# Lab_Controller_Board_v03.net
KiCad netlist of a schematic drawn in EAGLE
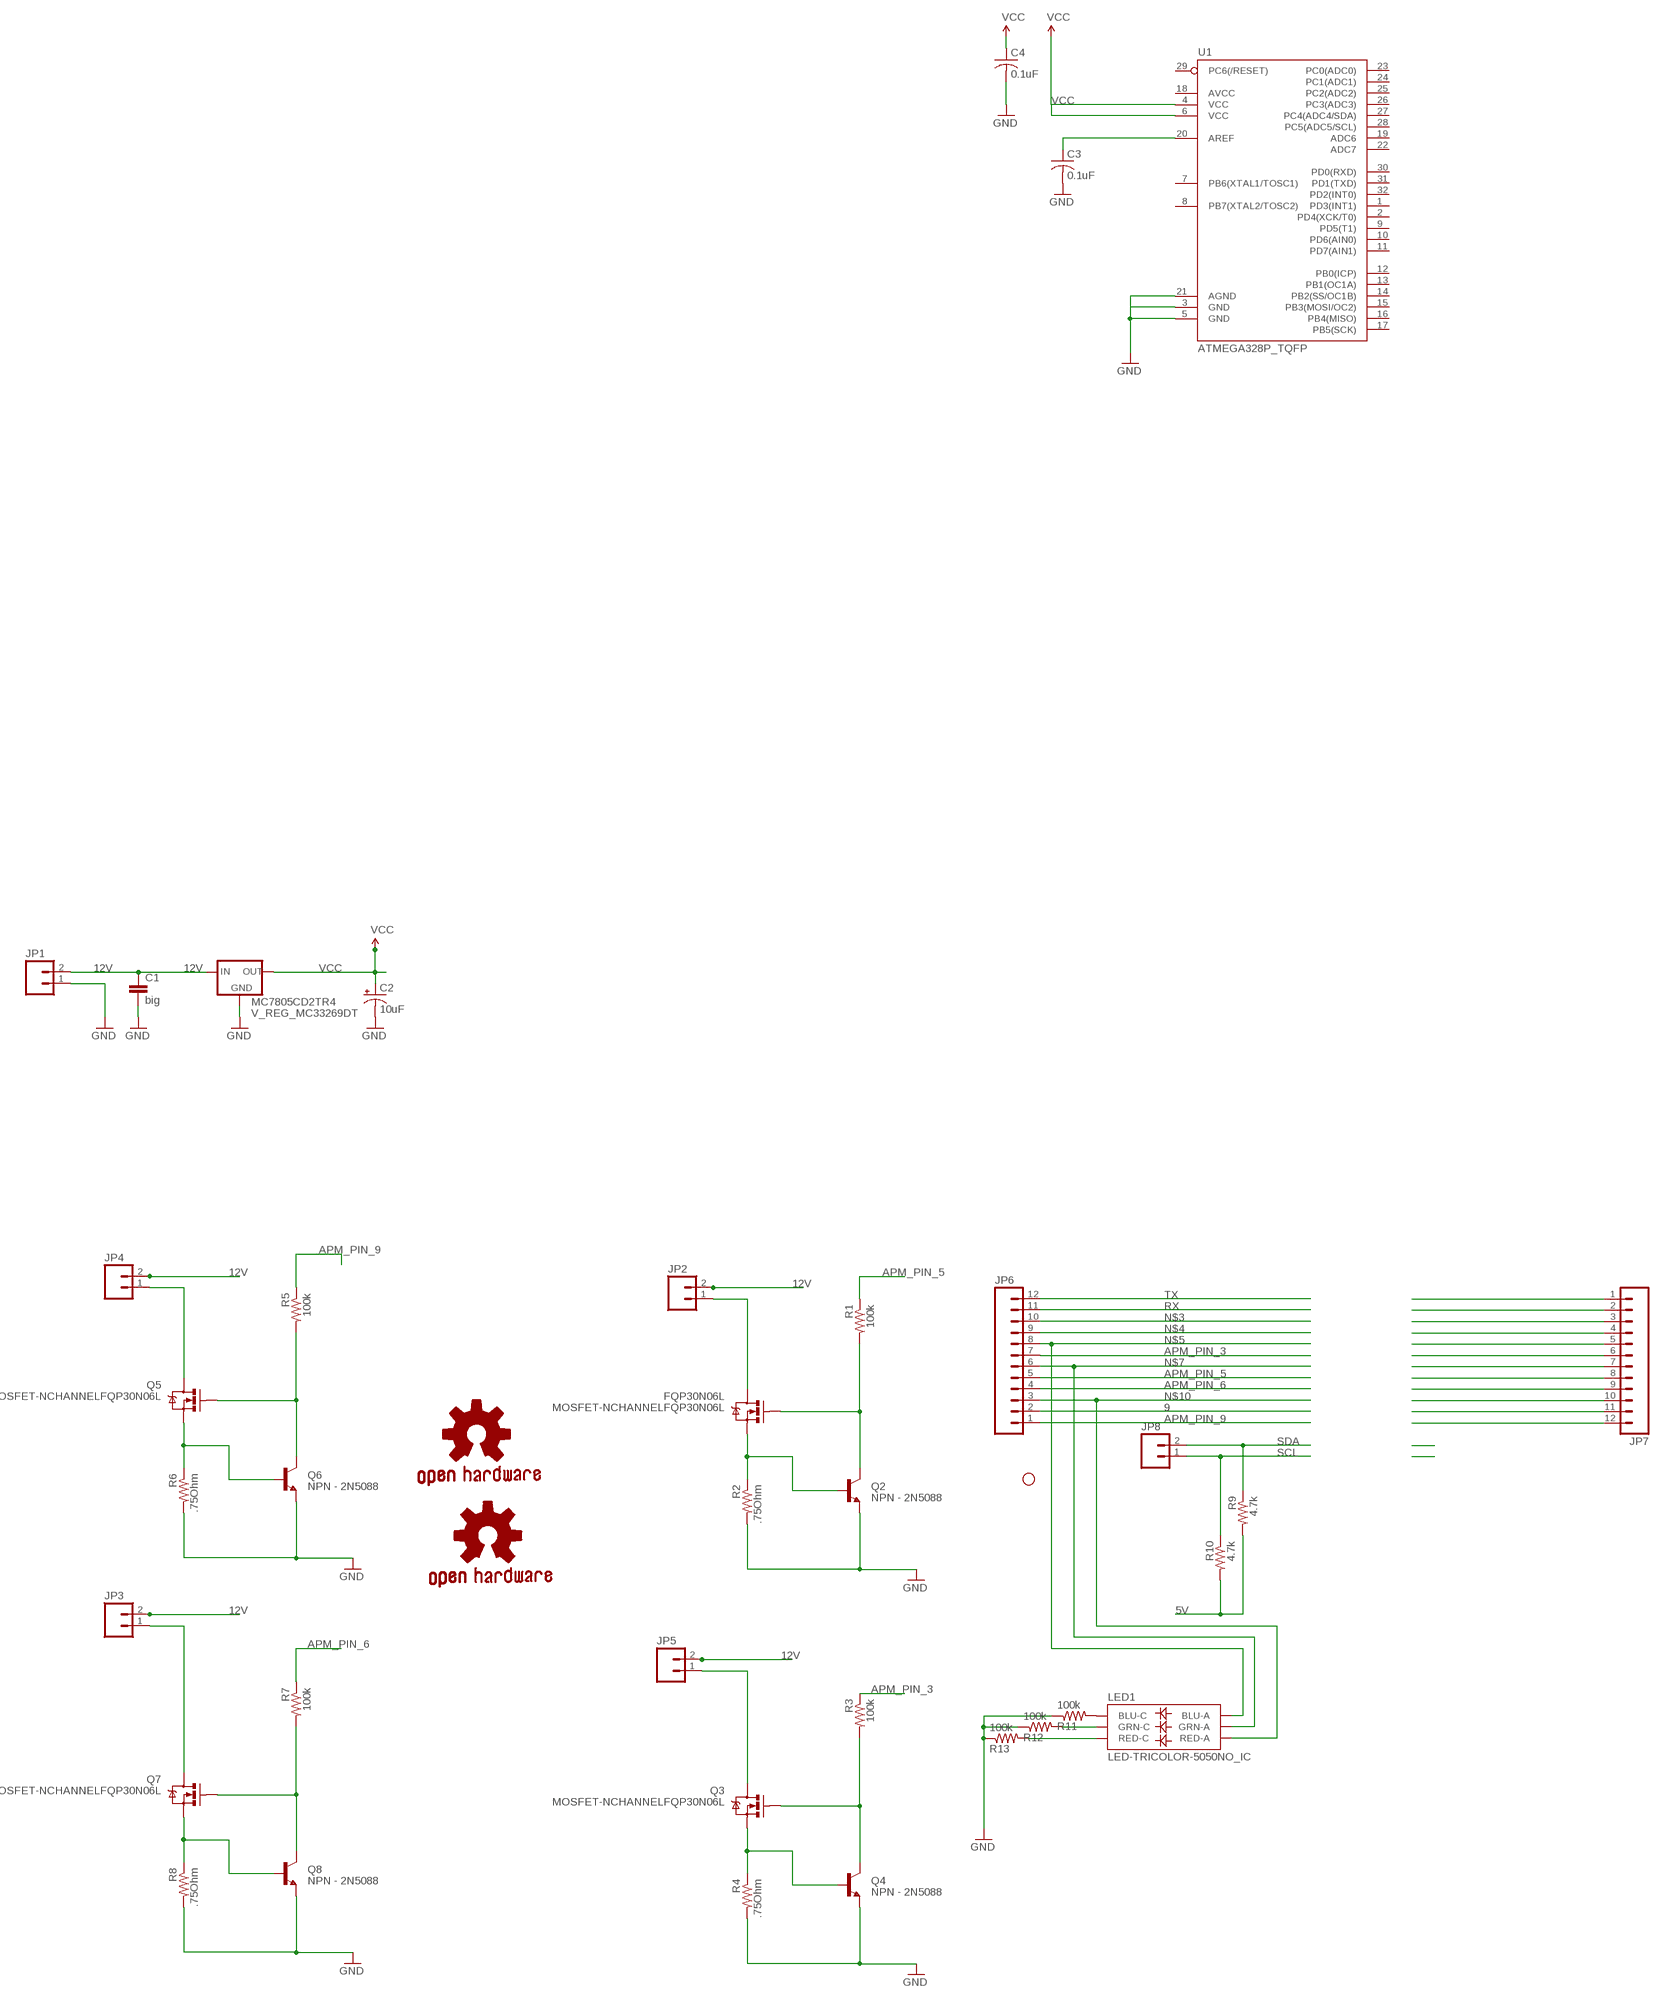
[diagram p0: schematic, sheet 1]

(export (version "E")
  (design (tool "Eeschema 10.0.6"))
  (components
    (comp (ref "C1")
      (value "big")
      (footprint "eagle-import:CAP-PTH-5MM")
      (libsource (lib "eagle-import") (part "CAPPTH1"))
    )
    (comp (ref "C2")
      (value "10uF")
      (footprint "eagle-import:EIA3528")
      (libsource (lib "eagle-import") (part "CAP_POL3528"))
    )
    (comp (ref "C3")
      (value "0.1uF")
      (footprint "eagle-import:C0402")
      (libsource (lib "eagle-import") (part "C-USC0402"))
    )
    (comp (ref "C4")
      (value "0.1uF")
      (footprint "eagle-import:C0402")
      (libsource (lib "eagle-import") (part "C-USC0402"))
    )
    (comp (ref "FQP30N06L")
      (value "MOSFET-NCHANNELFQP30N06L")
      (footprint "eagle-import:TO220V")
      (libsource (lib "eagle-import") (part "MOSFET-NCHANNELFQP30N06L"))
    )
    (comp (ref "GOLD_ORB_SM1")
      (value "OSHWLOGO_GOLD_ORB_MED")
      (footprint "eagle-import:OSHW1")
      (libsource (lib "eagle-import") (part "OSHWLOGO_GOLD_ORB_MED"))
    )
    (comp (ref "GOLD_ORB_SM2")
      (value "OSHWLOGO_GOLD_ORB_SM")
      (footprint "eagle-import:OSHW2")
      (libsource (lib "eagle-import") (part "OSHWLOGO_GOLD_ORB_SM"))
    )
    (comp (ref "JP1")
      (value "M025MM")
      (footprint "eagle-import:SCREWTERMINAL-5MM-2")
      (libsource (lib "eagle-import") (part "M025MM"))
    )
    (comp (ref "JP2")
      (value "M025MM")
      (footprint "eagle-import:SCREWTERMINAL-5MM-2")
      (libsource (lib "eagle-import") (part "M025MM"))
    )
    (comp (ref "JP3")
      (value "M025MM")
      (footprint "eagle-import:SCREWTERMINAL-5MM-2")
      (libsource (lib "eagle-import") (part "M025MM"))
    )
    (comp (ref "JP4")
      (value "M025MM")
      (footprint "eagle-import:SCREWTERMINAL-5MM-2")
      (libsource (lib "eagle-import") (part "M025MM"))
    )
    (comp (ref "JP5")
      (value "M025MM")
      (footprint "eagle-import:SCREWTERMINAL-5MM-2")
      (libsource (lib "eagle-import") (part "M025MM"))
    )
    (comp (ref "JP6")
      (value "M12PTH")
      (footprint "eagle-import:1X12")
      (libsource (lib "eagle-import") (part "M12PTH"))
    )
    (comp (ref "JP7")
      (value "M12PTH")
      (footprint "eagle-import:1X12")
      (libsource (lib "eagle-import") (part "M12PTH"))
    )
    (comp (ref "JP8")
      (value "M02LOCK")
      (footprint "eagle-import:1X02_LOCK")
      (libsource (lib "eagle-import") (part "M02LOCK"))
    )
    (comp (ref "LED1")
      (value "LED-TRICOLOR-5050NO_IC")
      (footprint "eagle-import:LED-TRICOLOR-5050")
      (libsource (lib "eagle-import") (part "LED-TRICOLOR-5050NO_IC"))
    )
    (comp (ref "MC7805CD2TR4")
      (value "V_REG_MC33269DT")
      (footprint "eagle-import:DPAK")
      (libsource (lib "eagle-import") (part "V_REG_MC33269DT"))
    )
    (comp (ref "Q2")
      (value "NPN - 2N5088")
      (footprint "eagle-import:TO-92")
      (libsource (lib "eagle-import") (part "TRANSISTOR_NPNTO92"))
    )
    (comp (ref "Q3")
      (value "MOSFET-NCHANNELFQP30N06L")
      (footprint "eagle-import:TO220V")
      (libsource (lib "eagle-import") (part "MOSFET-NCHANNELFQP30N06L"))
    )
    (comp (ref "Q4")
      (value "NPN - 2N5088")
      (footprint "eagle-import:TO-92")
      (libsource (lib "eagle-import") (part "TRANSISTOR_NPNTO92"))
    )
    (comp (ref "Q5")
      (value "MOSFET-NCHANNELFQP30N06L")
      (footprint "eagle-import:TO220V")
      (libsource (lib "eagle-import") (part "MOSFET-NCHANNELFQP30N06L"))
    )
    (comp (ref "Q6")
      (value "NPN - 2N5088")
      (footprint "eagle-import:TO-92")
      (libsource (lib "eagle-import") (part "TRANSISTOR_NPNTO92"))
    )
    (comp (ref "Q7")
      (value "MOSFET-NCHANNELFQP30N06L")
      (footprint "eagle-import:TO220V")
      (libsource (lib "eagle-import") (part "MOSFET-NCHANNELFQP30N06L"))
    )
    (comp (ref "Q8")
      (value "NPN - 2N5088")
      (footprint "eagle-import:TO-92")
      (libsource (lib "eagle-import") (part "TRANSISTOR_NPNTO92"))
    )
    (comp (ref "R1")
      (value "100k")
      (footprint "eagle-import:R0805W")
      (libsource (lib "eagle-import") (part "R-US_R0805W"))
    )
    (comp (ref "R2")
      (value ".75Ohm")
      (footprint "eagle-import:0411V")
      (libsource (lib "eagle-import") (part "R-US_0411/3V"))
    )
    (comp (ref "R3")
      (value "100k")
      (footprint "eagle-import:R0805W")
      (libsource (lib "eagle-import") (part "R-US_R0805W"))
    )
    (comp (ref "R4")
      (value ".75Ohm")
      (footprint "eagle-import:0411V")
      (libsource (lib "eagle-import") (part "R-US_0411/3V"))
    )
    (comp (ref "R5")
      (value "100k")
      (footprint "eagle-import:R0805W")
      (libsource (lib "eagle-import") (part "R-US_R0805W"))
    )
    (comp (ref "R6")
      (value ".75Ohm")
      (footprint "eagle-import:0411V")
      (libsource (lib "eagle-import") (part "R-US_0411/3V"))
    )
    (comp (ref "R7")
      (value "100k")
      (footprint "eagle-import:R0805W")
      (libsource (lib "eagle-import") (part "R-US_R0805W"))
    )
    (comp (ref "R8")
      (value ".75Ohm")
      (footprint "eagle-import:0411V")
      (libsource (lib "eagle-import") (part "R-US_0411/3V"))
    )
    (comp (ref "R9")
      (value "4.7k")
      (footprint "eagle-import:M0805")
      (libsource (lib "eagle-import") (part "R-US_M0805"))
    )
    (comp (ref "R10")
      (value "4.7k")
      (footprint "eagle-import:M0805")
      (libsource (lib "eagle-import") (part "R-US_M0805"))
    )
    (comp (ref "R11")
      (value "100k")
      (footprint "eagle-import:R0805W")
      (libsource (lib "eagle-import") (part "R-US_R0805W"))
    )
    (comp (ref "R12")
      (value "100k")
      (footprint "eagle-import:R0805W")
      (libsource (lib "eagle-import") (part "R-US_R0805W"))
    )
    (comp (ref "R13")
      (value "100k")
      (footprint "eagle-import:R0805W")
      (libsource (lib "eagle-import") (part "R-US_R0805W"))
    )
    (comp (ref "STANDOFF1")
      (value "STAND-OFF")
      (footprint "eagle-import:STAND-OFF")
      (libsource (lib "eagle-import") (part "STAND-OFF"))
    )
    (comp (ref "U1")
      (value "ATMEGA328P_TQFP")
      (footprint "eagle-import:TQFP32-08")
      (libsource (lib "eagle-import") (part "ATMEGA328P_TQFP"))
    )
  )
  (nets
    (net (code "1") (name "/5V") (class "Default")
      (node (ref "R10") (pin "2") (pinfunction "2_2") (pintype "passive"))
      (node (ref "R9") (pin "2") (pinfunction "2_2") (pintype "passive"))
    )
    (net (code "2") (name "/9") (class "Default")
      (node (ref "JP6") (pin "2") (pinfunction "2_2") (pintype "passive"))
    )
    (net (code "3") (name "/12V") (class "Default")
      (node (ref "C1") (pin "1") (pinfunction "1_1") (pintype "passive"))
      (node (ref "JP1") (pin "2") (pinfunction "2_2") (pintype "passive"))
      (node (ref "JP2") (pin "2") (pinfunction "2_2") (pintype "passive"))
      (node (ref "JP3") (pin "2") (pinfunction "2_2") (pintype "passive"))
      (node (ref "JP4") (pin "2") (pinfunction "2_2") (pintype "passive"))
      (node (ref "JP5") (pin "2") (pinfunction "2_2") (pintype "passive"))
      (node (ref "MC7805CD2TR4") (pin "3") (pinfunction "IN_3") (pintype "input"))
    )
    (net (code "4") (name "/APM_PIN_3") (class "Default")
      (node (ref "JP6") (pin "7") (pinfunction "7_7") (pintype "passive"))
      (node (ref "R3") (pin "1") (pinfunction "1_1") (pintype "passive"))
    )
    (net (code "5") (name "/APM_PIN_5") (class "Default")
      (node (ref "JP6") (pin "5") (pinfunction "5_5") (pintype "passive"))
      (node (ref "R1") (pin "1") (pinfunction "1_1") (pintype "passive"))
    )
    (net (code "6") (name "/APM_PIN_6") (class "Default")
      (node (ref "JP6") (pin "4") (pinfunction "4_4") (pintype "passive"))
      (node (ref "R7") (pin "1") (pinfunction "1_1") (pintype "passive"))
    )
    (net (code "7") (name "/APM_PIN_9") (class "Default")
      (node (ref "JP6") (pin "1") (pinfunction "1_1") (pintype "passive"))
      (node (ref "R5") (pin "1") (pinfunction "1_1") (pintype "passive"))
    )
    (net (code "8") (name "/N$3") (class "Default")
      (node (ref "JP6") (pin "10") (pinfunction "10_10") (pintype "passive"))
    )
    (net (code "9") (name "/N$4") (class "Default")
      (node (ref "JP6") (pin "9") (pinfunction "9_9") (pintype "passive"))
    )
    (net (code "10") (name "/N$5") (class "Default")
      (node (ref "JP6") (pin "8") (pinfunction "8_8") (pintype "passive"))
      (node (ref "LED1") (pin "3") (pinfunction "BLU-A_3") (pintype "bidirectional"))
    )
    (net (code "11") (name "/N$7") (class "Default")
      (node (ref "JP6") (pin "6") (pinfunction "6_6") (pintype "passive"))
      (node (ref "LED1") (pin "1") (pinfunction "GRN-A_1") (pintype "bidirectional"))
    )
    (net (code "12") (name "/N$10") (class "Default")
      (node (ref "JP6") (pin "3") (pinfunction "3_3") (pintype "passive"))
      (node (ref "LED1") (pin "2") (pinfunction "RED-A_2") (pintype "bidirectional"))
    )
    (net (code "13") (name "/RX") (class "Default")
      (node (ref "JP6") (pin "11") (pinfunction "11_11") (pintype "passive"))
    )
    (net (code "14") (name "/SCL") (class "Default")
      (node (ref "JP8") (pin "1") (pinfunction "1_1") (pintype "passive"))
      (node (ref "R10") (pin "1") (pinfunction "1_1") (pintype "passive"))
    )
    (net (code "15") (name "/SDA") (class "Default")
      (node (ref "JP8") (pin "2") (pinfunction "2_2") (pintype "passive"))
      (node (ref "R9") (pin "1") (pinfunction "1_1") (pintype "passive"))
    )
    (net (code "16") (name "/TX") (class "Default")
      (node (ref "JP6") (pin "12") (pinfunction "12_12") (pintype "passive"))
    )
    (net (code "17") (name "GND") (class "Default")
      (node (ref "C1") (pin "2") (pinfunction "2_2") (pintype "passive"))
      (node (ref "C2") (pin "C") (pinfunction "-_C") (pintype "passive"))
      (node (ref "C3") (pin "2") (pinfunction "2_2") (pintype "passive"))
      (node (ref "C4") (pin "2") (pinfunction "2_2") (pintype "passive"))
      (node (ref "JP1") (pin "1") (pinfunction "1_1") (pintype "passive"))
      (node (ref "MC7805CD2TR4") (pin "1") (pinfunction "GND_1") (pintype "input"))
      (node (ref "Q2") (pin "1") (pinfunction "E_1") (pintype "passive"))
      (node (ref "Q4") (pin "1") (pinfunction "E_1") (pintype "passive"))
      (node (ref "Q6") (pin "1") (pinfunction "E_1") (pintype "passive"))
      (node (ref "Q8") (pin "1") (pinfunction "E_1") (pintype "passive"))
      (node (ref "R11") (pin "1") (pinfunction "1_1") (pintype "passive"))
      (node (ref "R12") (pin "1") (pinfunction "1_1") (pintype "passive"))
      (node (ref "R13") (pin "1") (pinfunction "1_1") (pintype "passive"))
      (node (ref "R2") (pin "2") (pinfunction "2_2") (pintype "passive"))
      (node (ref "R4") (pin "2") (pinfunction "2_2") (pintype "passive"))
      (node (ref "R6") (pin "2") (pinfunction "2_2") (pintype "passive"))
      (node (ref "R8") (pin "2") (pinfunction "2_2") (pintype "passive"))
      (node (ref "U1") (pin "21") (pinfunction "AGND_21") (pintype "bidirectional"))
      (node (ref "U1") (pin "3") (pinfunction "GND_3") (pintype "bidirectional"))
      (node (ref "U1") (pin "5") (pinfunction "GND_5") (pintype "bidirectional"))
    )
    (net (code "18") (name "Net-(FQP30N06L-D)") (class "Default")
      (node (ref "FQP30N06L") (pin "2") (pinfunction "D_2") (pintype "passive"))
      (node (ref "JP2") (pin "1") (pinfunction "1_1") (pintype "passive"))
    )
    (net (code "19") (name "Net-(FQP30N06L-G)") (class "Default")
      (node (ref "FQP30N06L") (pin "1") (pinfunction "G_1") (pintype "passive"))
      (node (ref "Q2") (pin "3") (pinfunction "C_3") (pintype "passive"))
      (node (ref "R1") (pin "2") (pinfunction "2_2") (pintype "passive"))
    )
    (net (code "20") (name "Net-(FQP30N06L-S)") (class "Default")
      (node (ref "FQP30N06L") (pin "3") (pinfunction "S_3") (pintype "passive"))
      (node (ref "Q2") (pin "2") (pinfunction "B_2") (pintype "passive"))
      (node (ref "R2") (pin "1") (pinfunction "1_1") (pintype "passive"))
    )
    (net (code "21") (name "Net-(LED1-BLU-C)") (class "Default")
      (node (ref "LED1") (pin "4") (pinfunction "BLU-C_4") (pintype "bidirectional"))
      (node (ref "R11") (pin "2") (pinfunction "2_2") (pintype "passive"))
    )
    (net (code "22") (name "Net-(LED1-GRN-C)") (class "Default")
      (node (ref "LED1") (pin "6") (pinfunction "GRN-C_6") (pintype "bidirectional"))
      (node (ref "R12") (pin "2") (pinfunction "2_2") (pintype "passive"))
    )
    (net (code "23") (name "Net-(LED1-RED-C)") (class "Default")
      (node (ref "LED1") (pin "5") (pinfunction "RED-C_5") (pintype "bidirectional"))
      (node (ref "R13") (pin "2") (pinfunction "2_2") (pintype "passive"))
    )
    (net (code "24") (name "Net-(Q3-D)") (class "Default")
      (node (ref "JP5") (pin "1") (pinfunction "1_1") (pintype "passive"))
      (node (ref "Q3") (pin "2") (pinfunction "D_2") (pintype "passive"))
    )
    (net (code "25") (name "Net-(Q3-G)") (class "Default")
      (node (ref "Q3") (pin "1") (pinfunction "G_1") (pintype "passive"))
      (node (ref "Q4") (pin "3") (pinfunction "C_3") (pintype "passive"))
      (node (ref "R3") (pin "2") (pinfunction "2_2") (pintype "passive"))
    )
    (net (code "26") (name "Net-(Q3-S)") (class "Default")
      (node (ref "Q3") (pin "3") (pinfunction "S_3") (pintype "passive"))
      (node (ref "Q4") (pin "2") (pinfunction "B_2") (pintype "passive"))
      (node (ref "R4") (pin "1") (pinfunction "1_1") (pintype "passive"))
    )
    (net (code "27") (name "Net-(Q5-D)") (class "Default")
      (node (ref "JP4") (pin "1") (pinfunction "1_1") (pintype "passive"))
      (node (ref "Q5") (pin "2") (pinfunction "D_2") (pintype "passive"))
    )
    (net (code "28") (name "Net-(Q5-G)") (class "Default")
      (node (ref "Q5") (pin "1") (pinfunction "G_1") (pintype "passive"))
      (node (ref "Q6") (pin "3") (pinfunction "C_3") (pintype "passive"))
      (node (ref "R5") (pin "2") (pinfunction "2_2") (pintype "passive"))
    )
    (net (code "29") (name "Net-(Q5-S)") (class "Default")
      (node (ref "Q5") (pin "3") (pinfunction "S_3") (pintype "passive"))
      (node (ref "Q6") (pin "2") (pinfunction "B_2") (pintype "passive"))
      (node (ref "R6") (pin "1") (pinfunction "1_1") (pintype "passive"))
    )
    (net (code "30") (name "Net-(Q7-D)") (class "Default")
      (node (ref "JP3") (pin "1") (pinfunction "1_1") (pintype "passive"))
      (node (ref "Q7") (pin "2") (pinfunction "D_2") (pintype "passive"))
    )
    (net (code "31") (name "Net-(Q7-G)") (class "Default")
      (node (ref "Q7") (pin "1") (pinfunction "G_1") (pintype "passive"))
      (node (ref "Q8") (pin "3") (pinfunction "C_3") (pintype "passive"))
      (node (ref "R7") (pin "2") (pinfunction "2_2") (pintype "passive"))
    )
    (net (code "32") (name "Net-(Q7-S)") (class "Default")
      (node (ref "Q7") (pin "3") (pinfunction "S_3") (pintype "passive"))
      (node (ref "Q8") (pin "2") (pinfunction "B_2") (pintype "passive"))
      (node (ref "R8") (pin "1") (pinfunction "1_1") (pintype "passive"))
    )
    (net (code "33") (name "Net-(U1-AREF)") (class "Default")
      (node (ref "C3") (pin "1") (pinfunction "1_1") (pintype "passive"))
      (node (ref "U1") (pin "20") (pinfunction "AREF_20") (pintype "bidirectional"))
    )
    (net (code "34") (name "VCC") (class "Default")
      (node (ref "C2") (pin "A") (pinfunction "+_A") (pintype "passive"))
      (node (ref "C4") (pin "1") (pinfunction "1_1") (pintype "passive"))
      (node (ref "MC7805CD2TR4") (pin "4") (pinfunction "OUT_4") (pintype "passive"))
      (node (ref "U1") (pin "4") (pinfunction "VCC_4") (pintype "bidirectional"))
      (node (ref "U1") (pin "6") (pinfunction "VCC_6") (pintype "bidirectional"))
    )
    (net (code "35") (name "unconnected-(JP7-Pad1)") (class "Default")
      (node (ref "JP7") (pin "1") (pinfunction "1_1") (pintype "passive"))
    )
    (net (code "36") (name "unconnected-(JP7-Pad2)") (class "Default")
      (node (ref "JP7") (pin "2") (pinfunction "2_2") (pintype "passive"))
    )
    (net (code "37") (name "unconnected-(JP7-Pad3)") (class "Default")
      (node (ref "JP7") (pin "3") (pinfunction "3_3") (pintype "passive"))
    )
    (net (code "38") (name "unconnected-(JP7-Pad4)") (class "Default")
      (node (ref "JP7") (pin "4") (pinfunction "4_4") (pintype "passive"))
    )
    (net (code "39") (name "unconnected-(JP7-Pad5)") (class "Default")
      (node (ref "JP7") (pin "5") (pinfunction "5_5") (pintype "passive"))
    )
    (net (code "40") (name "unconnected-(JP7-Pad6)") (class "Default")
      (node (ref "JP7") (pin "6") (pinfunction "6_6") (pintype "passive"))
    )
    (net (code "41") (name "unconnected-(JP7-Pad7)") (class "Default")
      (node (ref "JP7") (pin "7") (pinfunction "7_7") (pintype "passive"))
    )
    (net (code "42") (name "unconnected-(JP7-Pad8)") (class "Default")
      (node (ref "JP7") (pin "8") (pinfunction "8_8") (pintype "passive"))
    )
    (net (code "43") (name "unconnected-(JP7-Pad9)") (class "Default")
      (node (ref "JP7") (pin "9") (pinfunction "9_9") (pintype "passive"))
    )
    (net (code "44") (name "unconnected-(JP7-Pad10)") (class "Default")
      (node (ref "JP7") (pin "10") (pinfunction "10_10") (pintype "passive"))
    )
    (net (code "45") (name "unconnected-(JP7-Pad11)") (class "Default")
      (node (ref "JP7") (pin "11") (pinfunction "11_11") (pintype "passive"))
    )
    (net (code "46") (name "unconnected-(JP7-Pad12)") (class "Default")
      (node (ref "JP7") (pin "12") (pinfunction "12_12") (pintype "passive"))
    )
    (net (code "47") (name "unconnected-(U1-ADC6-Pad19)") (class "Default")
      (node (ref "U1") (pin "19") (pinfunction "ADC6_19") (pintype "bidirectional"))
    )
    (net (code "48") (name "unconnected-(U1-ADC7-Pad22)") (class "Default")
      (node (ref "U1") (pin "22") (pinfunction "ADC7_22") (pintype "bidirectional"))
    )
    (net (code "49") (name "unconnected-(U1-AVCC-Pad18)") (class "Default")
      (node (ref "U1") (pin "18") (pinfunction "AVCC_18") (pintype "bidirectional"))
    )
    (net (code "50") (name "unconnected-(U1-PB0(ICP)-Pad12)") (class "Default")
      (node (ref "U1") (pin "12") (pinfunction "PB0(ICP)_12") (pintype "bidirectional"))
    )
    (net (code "51") (name "unconnected-(U1-PB1(OC1A)-Pad13)") (class "Default")
      (node (ref "U1") (pin "13") (pinfunction "PB1(OC1A)_13") (pintype "bidirectional"))
    )
    (net (code "52") (name "unconnected-(U1-PB2(SS{slash}OC1B)-Pad14)") (class "Default")
      (node (ref "U1") (pin "14") (pinfunction "PB2(SS/OC1B)_14") (pintype "bidirectional"))
    )
    (net (code "53") (name "unconnected-(U1-PB3(MOSI{slash}OC2)-Pad15)") (class "Default")
      (node (ref "U1") (pin "15") (pinfunction "PB3(MOSI/OC2)_15") (pintype "bidirectional"))
    )
    (net (code "54") (name "unconnected-(U1-PB4(MISO)-Pad16)") (class "Default")
      (node (ref "U1") (pin "16") (pinfunction "PB4(MISO)_16") (pintype "bidirectional"))
    )
    (net (code "55") (name "unconnected-(U1-PB5(SCK)-Pad17)") (class "Default")
      (node (ref "U1") (pin "17") (pinfunction "PB5(SCK)_17") (pintype "bidirectional"))
    )
    (net (code "56") (name "unconnected-(U1-PB6(XTAL1{slash}TOSC1)-Pad7)") (class "Default")
      (node (ref "U1") (pin "7") (pinfunction "PB6(XTAL1/TOSC1)_7") (pintype "bidirectional"))
    )
    (net (code "57") (name "unconnected-(U1-PB7(XTAL2{slash}TOSC2)-Pad8)") (class "Default")
      (node (ref "U1") (pin "8") (pinfunction "PB7(XTAL2/TOSC2)_8") (pintype "bidirectional"))
    )
    (net (code "58") (name "unconnected-(U1-PC0(ADC0)-Pad23)") (class "Default")
      (node (ref "U1") (pin "23") (pinfunction "PC0(ADC0)_23") (pintype "bidirectional"))
    )
    (net (code "59") (name "unconnected-(U1-PC1(ADC1)-Pad24)") (class "Default")
      (node (ref "U1") (pin "24") (pinfunction "PC1(ADC1)_24") (pintype "bidirectional"))
    )
    (net (code "60") (name "unconnected-(U1-PC2(ADC2)-Pad25)") (class "Default")
      (node (ref "U1") (pin "25") (pinfunction "PC2(ADC2)_25") (pintype "bidirectional"))
    )
    (net (code "61") (name "unconnected-(U1-PC3(ADC3)-Pad26)") (class "Default")
      (node (ref "U1") (pin "26") (pinfunction "PC3(ADC3)_26") (pintype "bidirectional"))
    )
    (net (code "62") (name "unconnected-(U1-PC4(ADC4{slash}SDA)-Pad27)") (class "Default")
      (node (ref "U1") (pin "27") (pinfunction "PC4(ADC4/SDA)_27") (pintype "bidirectional"))
    )
    (net (code "63") (name "unconnected-(U1-PC5(ADC5{slash}SCL)-Pad28)") (class "Default")
      (node (ref "U1") (pin "28") (pinfunction "PC5(ADC5/SCL)_28") (pintype "bidirectional"))
    )
    (net (code "64") (name "unconnected-(U1-PC6({slash}RESET)-Pad29)") (class "Default")
      (node (ref "U1") (pin "29") (pinfunction "PC6(/RESET)_29") (pintype "bidirectional"))
    )
    (net (code "65") (name "unconnected-(U1-PD0(RXD)-Pad30)") (class "Default")
      (node (ref "U1") (pin "30") (pinfunction "PD0(RXD)_30") (pintype "bidirectional"))
    )
    (net (code "66") (name "unconnected-(U1-PD1(TXD)-Pad31)") (class "Default")
      (node (ref "U1") (pin "31") (pinfunction "PD1(TXD)_31") (pintype "bidirectional"))
    )
    (net (code "67") (name "unconnected-(U1-PD2(INT0)-Pad32)") (class "Default")
      (node (ref "U1") (pin "32") (pinfunction "PD2(INT0)_32") (pintype "bidirectional"))
    )
    (net (code "68") (name "unconnected-(U1-PD3(INT1)-Pad1)") (class "Default")
      (node (ref "U1") (pin "1") (pinfunction "PD3(INT1)_1") (pintype "bidirectional"))
    )
    (net (code "69") (name "unconnected-(U1-PD4(XCK{slash}T0)-Pad2)") (class "Default")
      (node (ref "U1") (pin "2") (pinfunction "PD4(XCK/T0)_2") (pintype "bidirectional"))
    )
    (net (code "70") (name "unconnected-(U1-PD5(T1)-Pad9)") (class "Default")
      (node (ref "U1") (pin "9") (pinfunction "PD5(T1)_9") (pintype "bidirectional"))
    )
    (net (code "71") (name "unconnected-(U1-PD6(AIN0)-Pad10)") (class "Default")
      (node (ref "U1") (pin "10") (pinfunction "PD6(AIN0)_10") (pintype "bidirectional"))
    )
    (net (code "72") (name "unconnected-(U1-PD7(AIN1)-Pad11)") (class "Default")
      (node (ref "U1") (pin "11") (pinfunction "PD7(AIN1)_11") (pintype "bidirectional"))
    )
  )
)
